# hygrometer-probe.net
KiCad netlist of a schematic drawn in EasyEDA
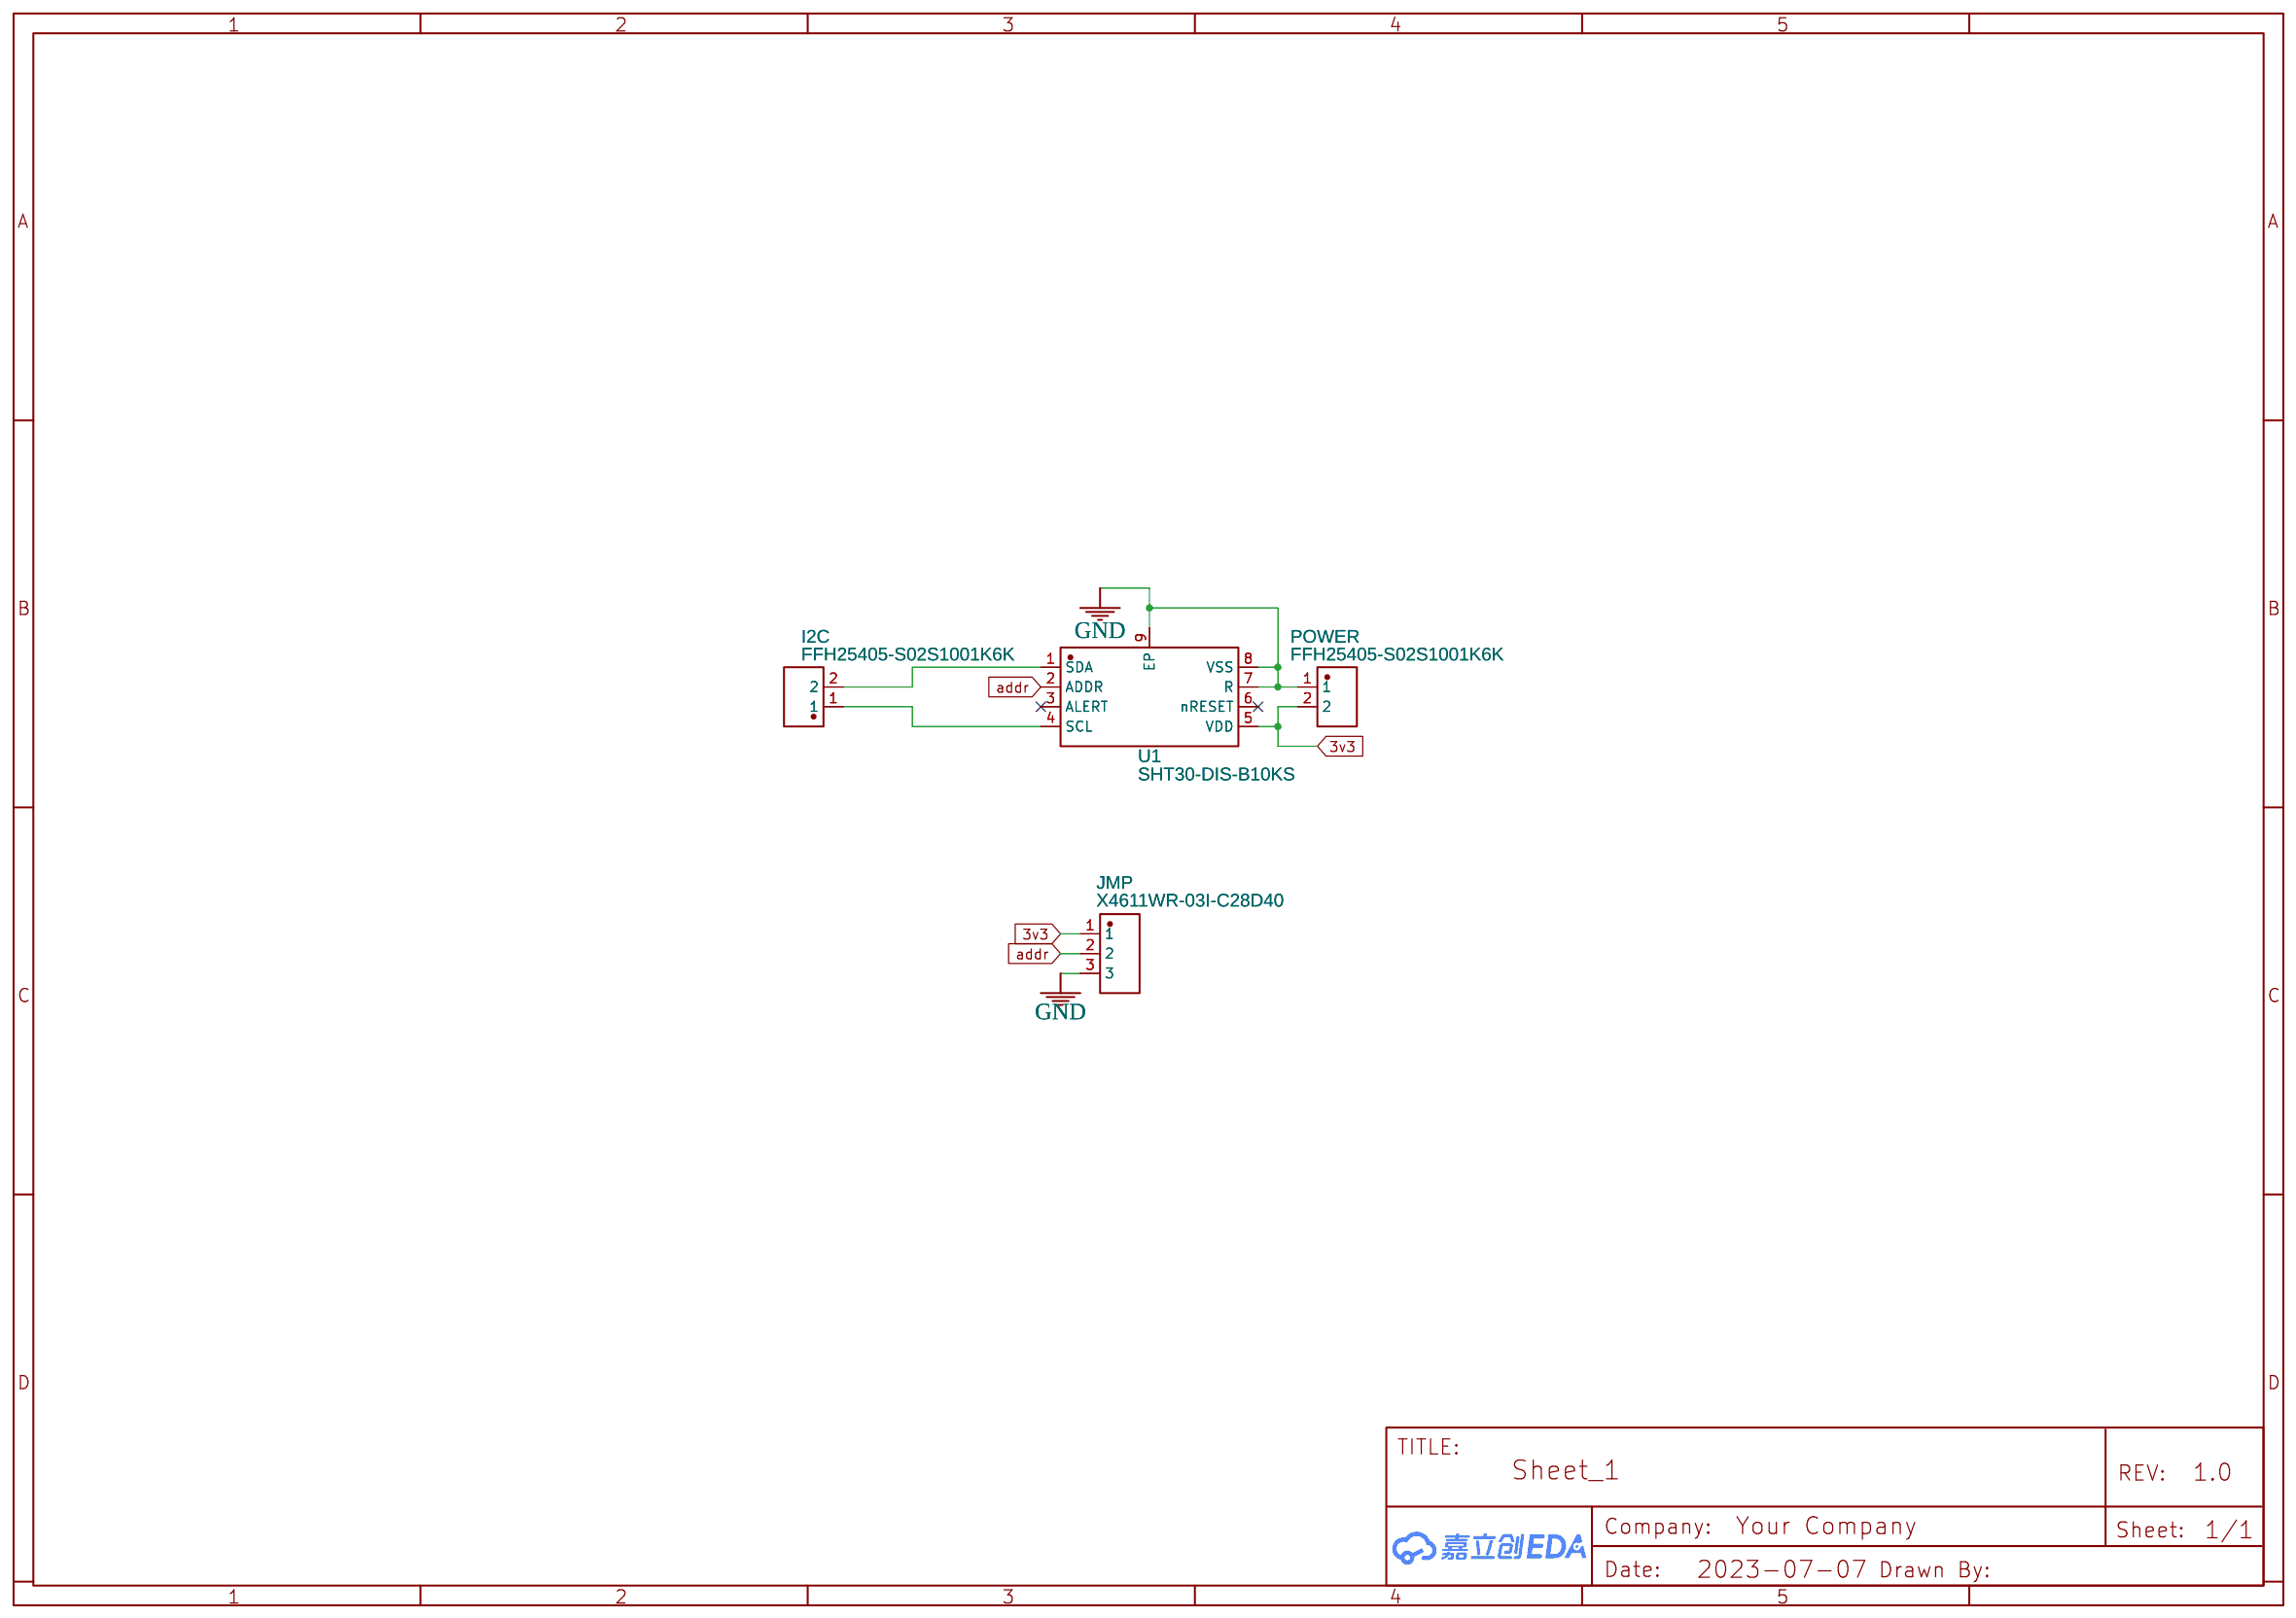
[diagram p0: schematic sheet]

(export (version "E")
  (design (tool "Eeschema 10.0.6"))
  (components
    (comp (ref "I2C")
      (value "FFH25405-S02S1001K6K")
      (fields (field (name "BOM_Supplier Part") "C2833813"))
      (libsource (lib "") (part "FFH25405-S02S1001K6K"))
    )
    (comp (ref "JMP")
      (value "X4611WR-03I-C28D40")
      (fields (field (name "BOM_Supplier Part") "C707012"))
      (libsource (lib "") (part "X4611WR-03I-C28D40"))
    )
    (comp (ref "POWER")
      (value "FFH25405-S02S1001K6K")
      (fields (field (name "BOM_Supplier Part") "C2833813"))
      (libsource (lib "") (part "FFH25405-S02S1001K6K_1"))
    )
    (comp (ref "U1")
      (value "SHT30-DIS-B10KS")
      (fields (field (name "BOM_Supplier Part") "C2687423"))
      (libsource (lib "") (part "SHT30-DIS-B10KS"))
    )
  )
  (nets
    (net (code "1") (name "3v3") (class "Default")
      (node (ref "JMP") (pin "1") (pinfunction "1_1") (pintype "unspecified"))
      (node (ref "POWER") (pin "2") (pinfunction "2_2") (pintype "unspecified"))
      (node (ref "U1") (pin "5") (pinfunction "VDD_5") (pintype "unspecified"))
    )
    (net (code "2") (name "GND") (class "Default")
      (node (ref "JMP") (pin "3") (pinfunction "3_3") (pintype "unspecified"))
      (node (ref "POWER") (pin "1") (pinfunction "1_1") (pintype "unspecified"))
      (node (ref "U1") (pin "7") (pinfunction "R_7") (pintype "unspecified"))
      (node (ref "U1") (pin "8") (pinfunction "VSS_8") (pintype "unspecified"))
      (node (ref "U1") (pin "9") (pinfunction "EP_9") (pintype "unspecified"))
    )
    (net (code "3") (name "Net-(U1-SCL)") (class "Default")
      (node (ref "I2C") (pin "1") (pinfunction "1_1") (pintype "unspecified"))
      (node (ref "U1") (pin "4") (pinfunction "SCL_4") (pintype "unspecified"))
    )
    (net (code "4") (name "Net-(U1-SDA)") (class "Default")
      (node (ref "I2C") (pin "2") (pinfunction "2_2") (pintype "unspecified"))
      (node (ref "U1") (pin "1") (pinfunction "SDA_1") (pintype "unspecified"))
    )
    (net (code "5") (name "addr") (class "Default")
      (node (ref "JMP") (pin "2") (pinfunction "2_2") (pintype "unspecified"))
      (node (ref "U1") (pin "2") (pinfunction "ADDR_2") (pintype "unspecified"))
    )
    (net (code "6") (name "unconnected-(U1-ALERT-Pad3)") (class "Default")
      (node (ref "U1") (pin "3") (pinfunction "ALERT_3") (pintype "unspecified+no_connect"))
    )
    (net (code "7") (name "unconnected-(U1-nRESET-Pad6)") (class "Default")
      (node (ref "U1") (pin "6") (pinfunction "nRESET_6") (pintype "unspecified+no_connect"))
    )
  )
)
